# pedals.net
KiCad netlist of a schematic drawn in EAGLE
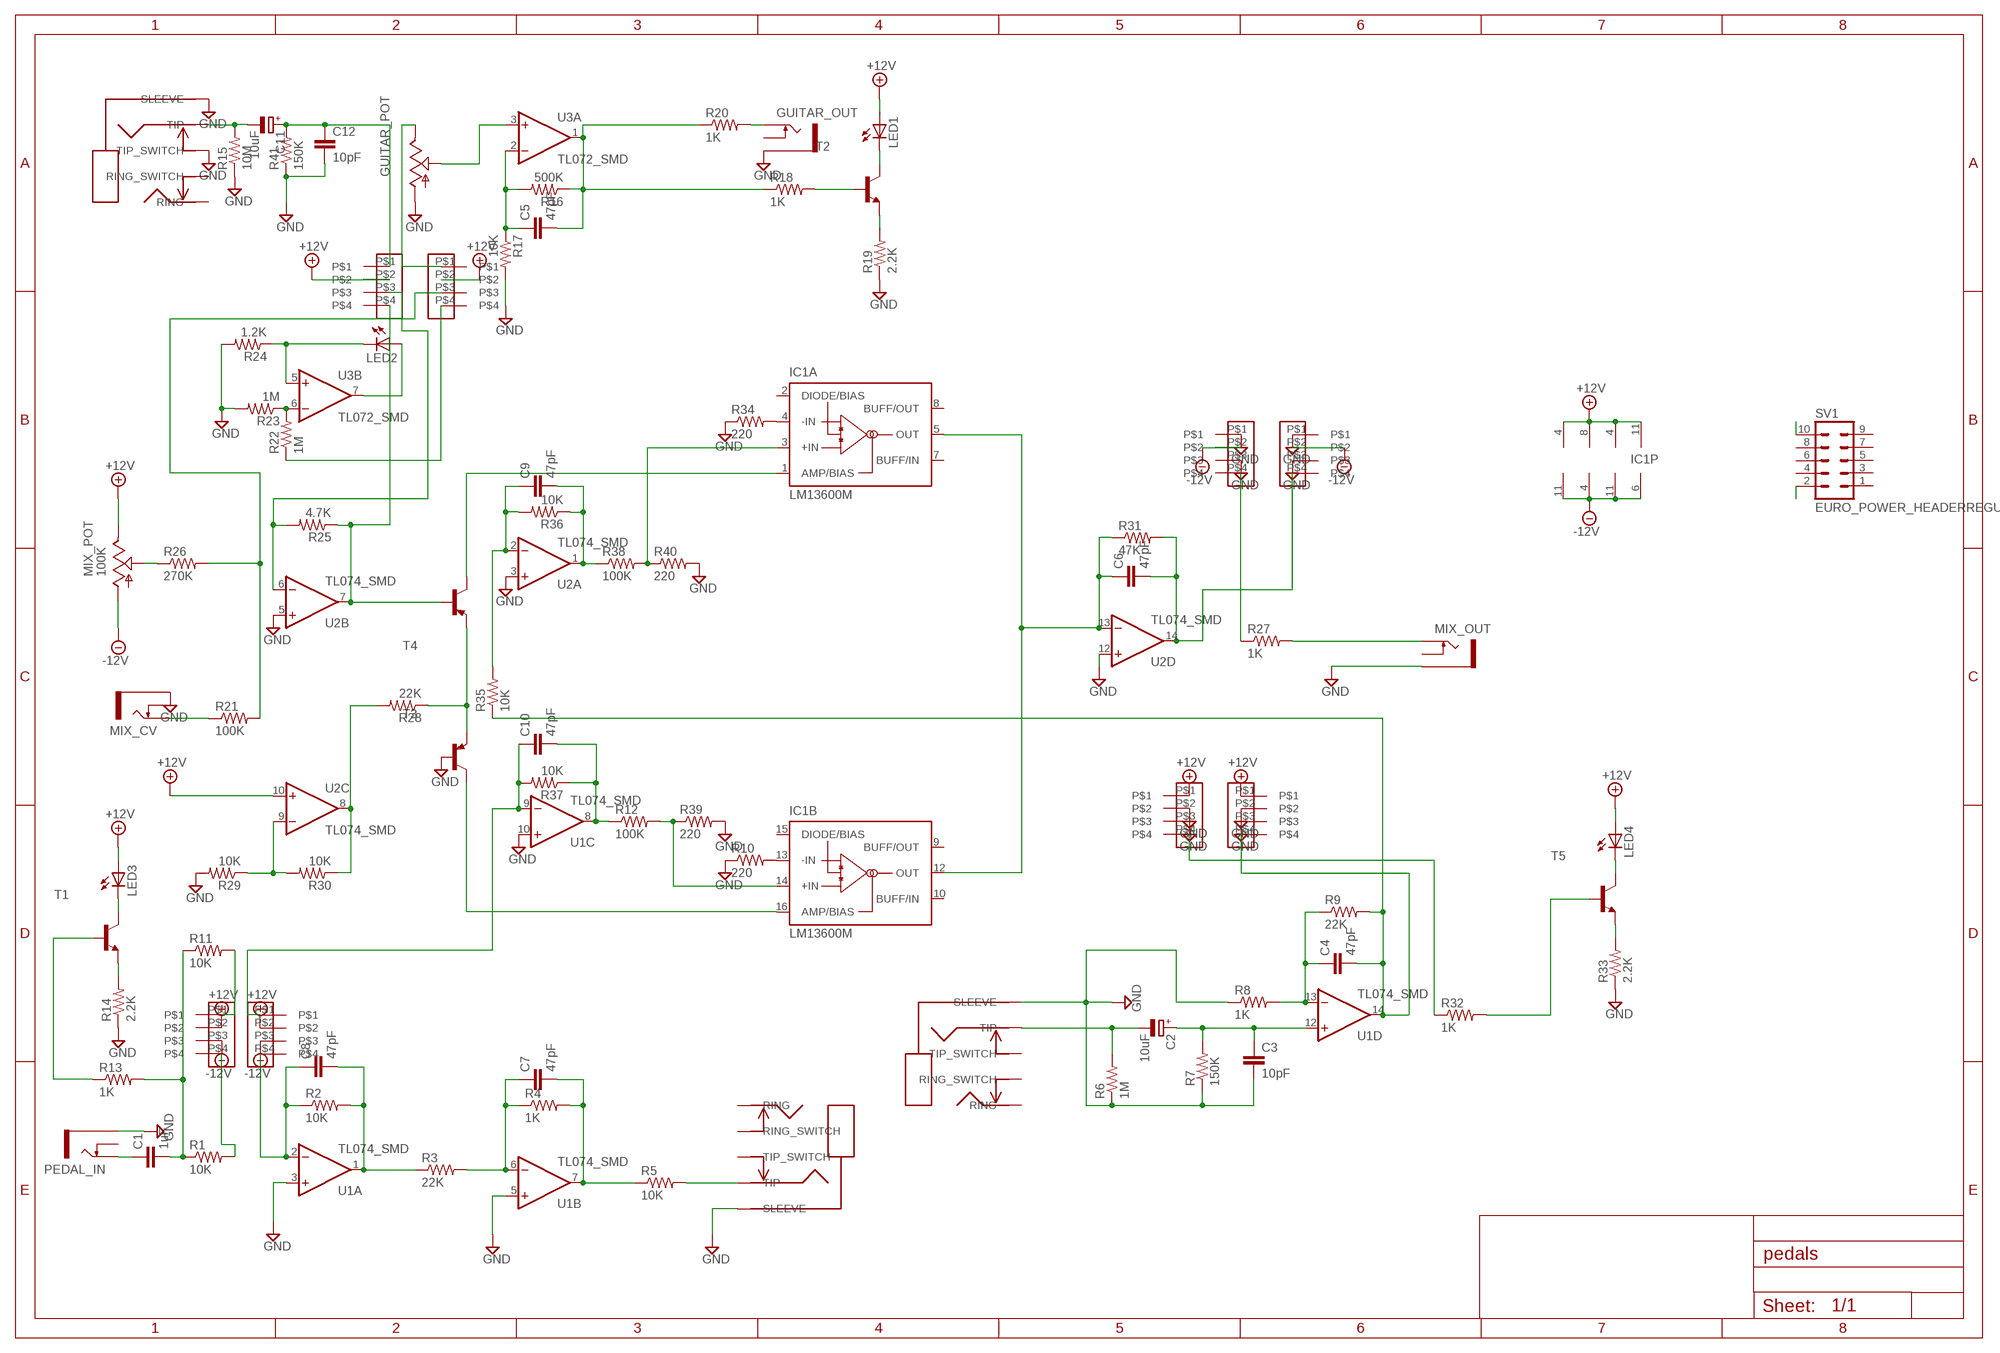
[diagram p0: schematic, sheet 1]

(export (version "E")
  (design (tool "Eeschema 10.0.6"))
  (components
    (comp (ref "C1")
      (value "1uF")
      (footprint "eagle-import:C0603")
      (libsource (lib "eagle-import") (part "C-EUC0603"))
    )
    (comp (ref "C2")
      (value "10uF")
      (footprint "eagle-import:PANASONIC_B")
      (libsource (lib "eagle-import") (part "CPOL-EUB"))
    )
    (comp (ref "C3")
      (value "10pF")
      (footprint "eagle-import:C0603")
      (libsource (lib "eagle-import") (part "C-EUC0603"))
    )
    (comp (ref "C4")
      (value "47pF")
      (footprint "eagle-import:C0603")
      (libsource (lib "eagle-import") (part "C-EUC0603"))
    )
    (comp (ref "C5")
      (value "47pF")
      (footprint "eagle-import:C0603")
      (libsource (lib "eagle-import") (part "C-EUC0603"))
    )
    (comp (ref "C6")
      (value "47pF")
      (footprint "eagle-import:C0603")
      (libsource (lib "eagle-import") (part "C-EUC0603"))
    )
    (comp (ref "C7")
      (value "47pF")
      (footprint "eagle-import:C0603")
      (libsource (lib "eagle-import") (part "C-EUC0603"))
    )
    (comp (ref "C8")
      (value "47pF")
      (footprint "eagle-import:C0603")
      (libsource (lib "eagle-import") (part "C-EUC0603"))
    )
    (comp (ref "C9")
      (value "47pF")
      (footprint "eagle-import:C0603")
      (libsource (lib "eagle-import") (part "C-EUC0603"))
    )
    (comp (ref "C10")
      (value "47pF")
      (footprint "eagle-import:C0603")
      (libsource (lib "eagle-import") (part "C-EUC0603"))
    )
    (comp (ref "C11")
      (value "10uF")
      (footprint "eagle-import:PANASONIC_B")
      (libsource (lib "eagle-import") (part "CPOL-EUB"))
    )
    (comp (ref "C12")
      (value "10pF")
      (footprint "eagle-import:C0603")
      (libsource (lib "eagle-import") (part "C-EUC0603"))
    )
    (comp (ref "GUITAR_INPUT")
      (value "WQP-PJ612A")
      (footprint "eagle-import:JACK")
      (libsource (lib "eagle-import") (part "WQP-PJ612A"))
    )
    (comp (ref "GUITAR_OUT")
      (value "THONKICONNNEW")
      (footprint "eagle-import:WQP-PJ301M-12_JACK")
      (libsource (lib "eagle-import") (part "THONKICONNNEW"))
    )
    (comp (ref "GUITAR_POT")
      (value "9MM_SNAP-IN_POT_")
      (footprint "eagle-import:9MM_SNAP-IN_POT")
      (libsource (lib "eagle-import") (part "9MM_SNAP-IN_POT_"))
    )
    (comp (ref "IC1")
      (value "LM13600M")
      (footprint "eagle-import:SO16")
      (libsource (lib "eagle-import") (part "LM13600M"))
    )
    (comp (ref "LB_B")
      (value "4PIN_HEADER")
      (footprint "eagle-import:4PIN")
      (libsource (lib "eagle-import") (part "4PIN_HEADER"))
    )
    (comp (ref "LB_O")
      (value "4PIN_HEADER")
      (footprint "eagle-import:4PIN")
      (libsource (lib "eagle-import") (part "4PIN_HEADER"))
    )
    (comp (ref "LED1")
      (value "LED3MM")
      (footprint "eagle-import:LED3MM")
      (libsource (lib "eagle-import") (part "LED3MM"))
    )
    (comp (ref "LED2")
      (value "LED3MM")
      (footprint "eagle-import:LED3MM")
      (libsource (lib "eagle-import") (part "LED3MM"))
    )
    (comp (ref "LED3")
      (value "LED3MM")
      (footprint "eagle-import:LED3MM")
      (libsource (lib "eagle-import") (part "LED3MM"))
    )
    (comp (ref "LED4")
      (value "LED3MM")
      (footprint "eagle-import:LED3MM")
      (libsource (lib "eagle-import") (part "led_259_LED3MM"))
    )
    (comp (ref "LO_B")
      (value "4PIN_HEADER")
      (footprint "eagle-import:4PIN")
      (libsource (lib "eagle-import") (part "4PIN_HEADER"))
    )
    (comp (ref "LO_O")
      (value "4PIN_HEADER")
      (footprint "eagle-import:4PIN")
      (libsource (lib "eagle-import") (part "4PIN_HEADER"))
    )
    (comp (ref "MIX_CV")
      (value "THONKICONNNEW")
      (footprint "eagle-import:WQP-PJ301M-12_JACK")
      (libsource (lib "eagle-import") (part "THONKICONNNEW"))
    )
    (comp (ref "MIX_OUT")
      (value "THONKICONNNEW")
      (footprint "eagle-import:WQP-PJ301M-12_JACK")
      (libsource (lib "eagle-import") (part "THONKICONNNEW"))
    )
    (comp (ref "MIX_POT")
      (value "100K")
      (footprint "eagle-import:9MM_SNAP-IN_POT")
      (libsource (lib "eagle-import") (part "9MM_SNAP-IN_POT_"))
    )
    (comp (ref "PEDAL-IN")
      (value "WQP-PJ612A")
      (footprint "eagle-import:JACK")
      (libsource (lib "eagle-import") (part "WQP-PJ612A"))
    )
    (comp (ref "PEDAL-OUT")
      (value "WQP-PJ612A")
      (footprint "eagle-import:JACK")
      (libsource (lib "eagle-import") (part "WQP-PJ612A"))
    )
    (comp (ref "PEDAL_IN")
      (value "THONKICONNNEW")
      (footprint "eagle-import:WQP-PJ301M-12_JACK")
      (libsource (lib "eagle-import") (part "THONKICONNNEW"))
    )
    (comp (ref "R1")
      (value "10K")
      (footprint "eagle-import:R0603")
      (libsource (lib "eagle-import") (part "R-US_R0603"))
    )
    (comp (ref "R2")
      (value "10K")
      (footprint "eagle-import:R0603")
      (libsource (lib "eagle-import") (part "R-US_R0603"))
    )
    (comp (ref "R3")
      (value "22K")
      (footprint "eagle-import:R0603")
      (libsource (lib "eagle-import") (part "R-US_R0603"))
    )
    (comp (ref "R4")
      (value "1K")
      (footprint "eagle-import:R0603")
      (libsource (lib "eagle-import") (part "R-US_R0603"))
    )
    (comp (ref "R5")
      (value "10K")
      (footprint "eagle-import:R0603")
      (libsource (lib "eagle-import") (part "R-US_R0603"))
    )
    (comp (ref "R6")
      (value "1M")
      (footprint "eagle-import:R0603")
      (libsource (lib "eagle-import") (part "R-US_R0603"))
    )
    (comp (ref "R7")
      (value "150K")
      (footprint "eagle-import:R0603")
      (libsource (lib "eagle-import") (part "R-US_R0603"))
    )
    (comp (ref "R8")
      (value "1K")
      (footprint "eagle-import:R0603")
      (libsource (lib "eagle-import") (part "R-US_R0603"))
    )
    (comp (ref "R9")
      (value "22K")
      (footprint "eagle-import:R0603")
      (libsource (lib "eagle-import") (part "R-US_R0603"))
    )
    (comp (ref "R10")
      (value "220")
      (footprint "eagle-import:R0603")
      (libsource (lib "eagle-import") (part "R-US_R0603"))
    )
    (comp (ref "R11")
      (value "10K")
      (footprint "eagle-import:R0603")
      (libsource (lib "eagle-import") (part "R-US_R0603"))
    )
    (comp (ref "R12")
      (value "100K")
      (footprint "eagle-import:R0603")
      (libsource (lib "eagle-import") (part "R-US_R0603"))
    )
    (comp (ref "R13")
      (value "1K")
      (footprint "eagle-import:R0603")
      (libsource (lib "eagle-import") (part "R-US_R0603"))
    )
    (comp (ref "R14")
      (value "2.2K")
      (footprint "eagle-import:R0603")
      (libsource (lib "eagle-import") (part "R-US_R0603"))
    )
    (comp (ref "R15")
      (value "10M")
      (footprint "eagle-import:R0603")
      (libsource (lib "eagle-import") (part "R-US_R0603"))
    )
    (comp (ref "R16")
      (value "500K")
      (footprint "eagle-import:R0603")
      (libsource (lib "eagle-import") (part "R-US_R0603"))
    )
    (comp (ref "R17")
      (value "10K")
      (footprint "eagle-import:R0603")
      (libsource (lib "eagle-import") (part "R-US_R0603"))
    )
    (comp (ref "R18")
      (value "1K")
      (footprint "eagle-import:R0603")
      (libsource (lib "eagle-import") (part "R-US_R0603"))
    )
    (comp (ref "R19")
      (value "2.2K")
      (footprint "eagle-import:R0603")
      (libsource (lib "eagle-import") (part "R-US_R0603"))
    )
    (comp (ref "R20")
      (value "1K")
      (footprint "eagle-import:R0603")
      (libsource (lib "eagle-import") (part "R-US_R0603"))
    )
    (comp (ref "R21")
      (value "100K")
      (footprint "eagle-import:R0603")
      (libsource (lib "eagle-import") (part "R-US_R0603"))
    )
    (comp (ref "R22")
      (value "1M")
      (footprint "eagle-import:R0603")
      (libsource (lib "eagle-import") (part "R-US_R0603"))
    )
    (comp (ref "R23")
      (value "1M")
      (footprint "eagle-import:R0603")
      (libsource (lib "eagle-import") (part "R-US_R0603"))
    )
    (comp (ref "R24")
      (value "1.2K")
      (footprint "eagle-import:R0603")
      (libsource (lib "eagle-import") (part "R-US_R0603"))
    )
    (comp (ref "R25")
      (value "4.7K")
      (footprint "eagle-import:R0603")
      (libsource (lib "eagle-import") (part "R-US_R0603"))
    )
    (comp (ref "R26")
      (value "270K")
      (footprint "eagle-import:R0603")
      (libsource (lib "eagle-import") (part "R-US_R0603"))
    )
    (comp (ref "R27")
      (value "1K")
      (footprint "eagle-import:R0603")
      (libsource (lib "eagle-import") (part "R-US_R0603"))
    )
    (comp (ref "R28")
      (value "22K")
      (footprint "eagle-import:R0603")
      (libsource (lib "eagle-import") (part "R-US_R0603"))
    )
    (comp (ref "R29")
      (value "10K")
      (footprint "eagle-import:R0603")
      (libsource (lib "eagle-import") (part "R-US_R0603"))
    )
    (comp (ref "R30")
      (value "10K")
      (footprint "eagle-import:R0603")
      (libsource (lib "eagle-import") (part "R-US_R0603"))
    )
    (comp (ref "R31")
      (value "47K")
      (footprint "eagle-import:R0603")
      (libsource (lib "eagle-import") (part "R-US_R0603"))
    )
    (comp (ref "R32")
      (value "1K")
      (footprint "eagle-import:R0603")
      (libsource (lib "eagle-import") (part "R-US_R0603"))
    )
    (comp (ref "R33")
      (value "2.2K")
      (footprint "eagle-import:R0603")
      (libsource (lib "eagle-import") (part "R-US_R0603"))
    )
    (comp (ref "R34")
      (value "220")
      (footprint "eagle-import:R0603")
      (libsource (lib "eagle-import") (part "R-US_R0603"))
    )
    (comp (ref "R35")
      (value "10K")
      (footprint "eagle-import:R0603")
      (libsource (lib "eagle-import") (part "R-US_R0603"))
    )
    (comp (ref "R36")
      (value "10K")
      (footprint "eagle-import:R0603")
      (libsource (lib "eagle-import") (part "R-US_R0603"))
    )
    (comp (ref "R37")
      (value "10K")
      (footprint "eagle-import:R0603")
      (libsource (lib "eagle-import") (part "R-US_R0603"))
    )
    (comp (ref "R38")
      (value "100K")
      (footprint "eagle-import:R0603")
      (libsource (lib "eagle-import") (part "R-US_R0603"))
    )
    (comp (ref "R39")
      (value "220")
      (footprint "eagle-import:R0603")
      (libsource (lib "eagle-import") (part "R-US_R0603"))
    )
    (comp (ref "R40")
      (value "220")
      (footprint "eagle-import:R0603")
      (libsource (lib "eagle-import") (part "R-US_R0603"))
    )
    (comp (ref "R41")
      (value "150K")
      (footprint "eagle-import:R0603")
      (libsource (lib "eagle-import") (part "R-US_R0603"))
    )
    (comp (ref "RB_B")
      (value "4PIN_HEADER")
      (footprint "eagle-import:4PIN")
      (libsource (lib "eagle-import") (part "4PIN_HEADER"))
    )
    (comp (ref "RB_O")
      (value "4PIN_HEADER")
      (footprint "eagle-import:4PIN")
      (libsource (lib "eagle-import") (part "4PIN_HEADER"))
    )
    (comp (ref "RO_B")
      (value "4PIN_HEADER")
      (footprint "eagle-import:4PIN")
      (libsource (lib "eagle-import") (part "4PIN_HEADER"))
    )
    (comp (ref "RO_O")
      (value "4PIN_HEADER")
      (footprint "eagle-import:4PIN")
      (libsource (lib "eagle-import") (part "4PIN_HEADER"))
    )
    (comp (ref "SV1")
      (value "EURO_POWER_HEADERREGULAR")
      (footprint "eagle-import:EURO_POWER_HEADER")
      (libsource (lib "eagle-import") (part "EURO_POWER_HEADERREGULAR"))
    )
    (comp (ref "T1")
      (value "MMBT3904LT1-NPN-SOT23-BEC")
      (footprint "eagle-import:SOT23-BEC")
      (libsource (lib "eagle-import") (part "-NPN-SOT23-BECMMBT3904LT1"))
    )
    (comp (ref "T2")
      (value "MMBT3904LT1-NPN-SOT23-BEC")
      (footprint "eagle-import:SOT23-BEC")
      (libsource (lib "eagle-import") (part "-NPN-SOT23-BECMMBT3904LT1"))
    )
    (comp (ref "T3")
      (value "BC857A-PNP-SOT23-BEC")
      (footprint "eagle-import:SOT23-BEC")
      (libsource (lib "eagle-import") (part "-PNP-SOT23-BECBC857A"))
    )
    (comp (ref "T4")
      (value "BC857A-PNP-SOT23-BEC")
      (footprint "eagle-import:SOT23-BEC")
      (libsource (lib "eagle-import") (part "-PNP-SOT23-BECBC857A"))
    )
    (comp (ref "T5")
      (value "MMBT3904LT1-NPN-SOT23-BEC")
      (footprint "eagle-import:SOT23-BEC")
      (libsource (lib "eagle-import") (part "-NPN-SOT23-BECMMBT3904LT1"))
    )
    (comp (ref "U1")
      (value "TL074_SMD")
      (footprint "eagle-import:SO14")
      (libsource (lib "eagle-import") (part "TL074_SMD"))
    )
    (comp (ref "U2")
      (value "TL074_SMD")
      (footprint "eagle-import:SO14")
      (libsource (lib "eagle-import") (part "TL074_SMD"))
    )
    (comp (ref "U3")
      (value "TL072_SMD")
      (footprint "eagle-import:SO08")
      (libsource (lib "eagle-import") (part "TL072_SMD"))
    )
  )
  (nets
    (net (code "1") (name "+12V") (class "Default")
      (node (ref "IC1") (pin "11") (pinfunction "V+_11") (pintype "power_in"))
      (node (ref "LB_B") (pin "P$2") (pinfunction "P$2_P$2") (pintype "bidirectional"))
      (node (ref "LB_O") (pin "P$2") (pinfunction "P$2_P$2") (pintype "bidirectional"))
      (node (ref "LED1") (pin "A") (pinfunction "A_A") (pintype "passive"))
      (node (ref "LED3") (pin "A") (pinfunction "A_A") (pintype "passive"))
      (node (ref "LED4") (pin "A") (pinfunction "A_A") (pintype "passive"))
      (node (ref "LO_B") (pin "P$2") (pinfunction "P$2_P$2") (pintype "bidirectional"))
      (node (ref "LO_O") (pin "P$2") (pinfunction "P$2_P$2") (pintype "bidirectional"))
      (node (ref "MIX_POT") (pin "3") (pinfunction "E_3") (pintype "passive"))
      (node (ref "RO_B") (pin "P$1") (pinfunction "P$1_P$1") (pintype "bidirectional"))
      (node (ref "RO_O") (pin "P$1") (pinfunction "P$1_P$1") (pintype "bidirectional"))
      (node (ref "U1") (pin "4") (pinfunction "V+_4") (pintype "power_in"))
      (node (ref "U2") (pin "10") (pinfunction "+IN_10") (pintype "input"))
      (node (ref "U2") (pin "4") (pinfunction "V+_4") (pintype "power_in"))
      (node (ref "U3") (pin "8") (pinfunction "V+_8") (pintype "power_in"))
    )
    (net (code "2") (name "-12V") (class "Default")
      (node (ref "IC1") (pin "6") (pinfunction "V-_6") (pintype "power_in"))
      (node (ref "LO_B") (pin "P$3") (pinfunction "P$3_P$3") (pintype "bidirectional"))
      (node (ref "LO_O") (pin "P$3") (pinfunction "P$3_P$3") (pintype "bidirectional"))
      (node (ref "MIX_POT") (pin "1") (pinfunction "A_1") (pintype "passive"))
      (node (ref "RB_B") (pin "P$2") (pinfunction "P$2_P$2") (pintype "bidirectional"))
      (node (ref "RB_O") (pin "P$2") (pinfunction "P$2_P$2") (pintype "bidirectional"))
      (node (ref "U1") (pin "11") (pinfunction "V-_11") (pintype "power_in"))
      (node (ref "U2") (pin "11") (pinfunction "V-_11") (pintype "power_in"))
      (node (ref "U3") (pin "4") (pinfunction "V-_4") (pintype "power_in"))
    )
    (net (code "3") (name "GND") (class "Default")
      (node (ref "C12") (pin "2") (pinfunction "2_2") (pintype "passive"))
      (node (ref "C3") (pin "2") (pinfunction "2_2") (pintype "passive"))
      (node (ref "GUITAR_INPUT") (pin "PIN1") (pinfunction "SLEEVE_PIN1") (pintype "output"))
      (node (ref "GUITAR_INPUT") (pin "PIN5") (pinfunction "TIP_SWITCH_PIN5") (pintype "input"))
      (node (ref "GUITAR_OUT") (pin "P$3_SLEEVE") (pinfunction "SLEEVE_P$3_SLEEVE") (pintype "passive"))
      (node (ref "GUITAR_POT") (pin "1") (pinfunction "A_1") (pintype "passive"))
      (node (ref "MIX_CV") (pin "P$3_SLEEVE") (pinfunction "SLEEVE_P$3_SLEEVE") (pintype "passive"))
      (node (ref "MIX_OUT") (pin "P$3_SLEEVE") (pinfunction "SLEEVE_P$3_SLEEVE") (pintype "passive"))
      (node (ref "PEDAL-IN") (pin "PIN1") (pinfunction "SLEEVE_PIN1") (pintype "output"))
      (node (ref "PEDAL-OUT") (pin "PIN1") (pinfunction "SLEEVE_PIN1") (pintype "output"))
      (node (ref "PEDAL_IN") (pin "P$3_SLEEVE") (pinfunction "SLEEVE_P$3_SLEEVE") (pintype "passive"))
      (node (ref "R10") (pin "1") (pinfunction "1_1") (pintype "passive"))
      (node (ref "R14") (pin "1") (pinfunction "1_1") (pintype "passive"))
      (node (ref "R15") (pin "1") (pinfunction "1_1") (pintype "passive"))
      (node (ref "R17") (pin "2") (pinfunction "2_2") (pintype "passive"))
      (node (ref "R19") (pin "1") (pinfunction "1_1") (pintype "passive"))
      (node (ref "R23") (pin "2") (pinfunction "2_2") (pintype "passive"))
      (node (ref "R24") (pin "2") (pinfunction "2_2") (pintype "passive"))
      (node (ref "R29") (pin "2") (pinfunction "2_2") (pintype "passive"))
      (node (ref "R33") (pin "1") (pinfunction "1_1") (pintype "passive"))
      (node (ref "R34") (pin "1") (pinfunction "1_1") (pintype "passive"))
      (node (ref "R39") (pin "2") (pinfunction "2_2") (pintype "passive"))
      (node (ref "R40") (pin "2") (pinfunction "2_2") (pintype "passive"))
      (node (ref "R41") (pin "1") (pinfunction "1_1") (pintype "passive"))
      (node (ref "R6") (pin "1") (pinfunction "1_1") (pintype "passive"))
      (node (ref "R7") (pin "1") (pinfunction "1_1") (pintype "passive"))
      (node (ref "R8") (pin "1") (pinfunction "1_1") (pintype "passive"))
      (node (ref "RB_B") (pin "P$1") (pinfunction "P$1_P$1") (pintype "bidirectional"))
      (node (ref "RB_B") (pin "P$3") (pinfunction "P$3_P$3") (pintype "bidirectional"))
      (node (ref "RB_O") (pin "P$1") (pinfunction "P$1_P$1") (pintype "bidirectional"))
      (node (ref "RB_O") (pin "P$3") (pinfunction "P$3_P$3") (pintype "bidirectional"))
      (node (ref "RO_B") (pin "P$2") (pinfunction "P$2_P$2") (pintype "bidirectional"))
      (node (ref "RO_B") (pin "P$3") (pinfunction "P$3_P$3") (pintype "bidirectional"))
      (node (ref "RO_O") (pin "P$2") (pinfunction "P$2_P$2") (pintype "bidirectional"))
      (node (ref "RO_O") (pin "P$3") (pinfunction "P$3_P$3") (pintype "bidirectional"))
      (node (ref "T3") (pin "B") (pinfunction "B_B") (pintype "passive"))
      (node (ref "U1") (pin "10") (pinfunction "+IN_10") (pintype "input"))
      (node (ref "U1") (pin "3") (pinfunction "+IN_3") (pintype "input"))
      (node (ref "U1") (pin "5") (pinfunction "+IN_5") (pintype "input"))
      (node (ref "U2") (pin "12") (pinfunction "+IN_12") (pintype "input"))
      (node (ref "U2") (pin "3") (pinfunction "+IN_3") (pintype "input"))
      (node (ref "U2") (pin "5") (pinfunction "+IN_5") (pintype "input"))
    )
    (net (code "4") (name "Net-(C1-Pad2)") (class "Default")
      (node (ref "C1") (pin "2") (pinfunction "2_2") (pintype "passive"))
      (node (ref "R1") (pin "1") (pinfunction "1_1") (pintype "passive"))
      (node (ref "R11") (pin "1") (pinfunction "1_1") (pintype "passive"))
      (node (ref "R13") (pin "2") (pinfunction "2_2") (pintype "passive"))
    )
    (net (code "5") (name "Net-(C11-Pad+)") (class "Default")
      (node (ref "C11") (pin "+") (pinfunction "+_+") (pintype "passive"))
      (node (ref "C12") (pin "1") (pinfunction "1_1") (pintype "passive"))
      (node (ref "LB_O") (pin "P$1") (pinfunction "P$1_P$1") (pintype "bidirectional"))
      (node (ref "R41") (pin "2") (pinfunction "2_2") (pintype "passive"))
    )
    (net (code "6") (name "Net-(GUITAR_INPUT-TIP)") (class "Default")
      (node (ref "C11") (pin "-") (pinfunction "-_-") (pintype "passive"))
      (node (ref "GUITAR_INPUT") (pin "PIN3") (pinfunction "TIP_PIN3") (pintype "output"))
      (node (ref "R15") (pin "2") (pinfunction "2_2") (pintype "passive"))
    )
    (net (code "7") (name "Net-(GUITAR_OUT-TIP)") (class "Default")
      (node (ref "GUITAR_OUT") (pin "P$1_TIP") (pinfunction "TIP_P$1_TIP") (pintype "passive"))
      (node (ref "R20") (pin "2") (pinfunction "2_2") (pintype "passive"))
    )
    (net (code "8") (name "Net-(GUITAR_POT-E)") (class "Default")
      (node (ref "GUITAR_POT") (pin "3") (pinfunction "E_3") (pintype "passive"))
      (node (ref "LB_B") (pin "P$1") (pinfunction "P$1_P$1") (pintype "bidirectional"))
    )
    (net (code "9") (name "Net-(GUITAR_POT-S)") (class "Default")
      (node (ref "GUITAR_POT") (pin "2") (pinfunction "S_2") (pintype "passive"))
      (node (ref "U3") (pin "3") (pinfunction "+IN_3") (pintype "input"))
    )
    (net (code "10") (name "Net-(IC1A-+IN)") (class "Default")
      (node (ref "IC1") (pin "3") (pinfunction "+IN_3") (pintype "input"))
      (node (ref "R38") (pin "2") (pinfunction "2_2") (pintype "passive"))
      (node (ref "R40") (pin "1") (pinfunction "1_1") (pintype "passive"))
    )
    (net (code "11") (name "Net-(IC1A--IN)") (class "Default")
      (node (ref "IC1") (pin "4") (pinfunction "-IN_4") (pintype "input"))
      (node (ref "R34") (pin "2") (pinfunction "2_2") (pintype "passive"))
    )
    (net (code "12") (name "Net-(IC1A-AMP{slash}BIAS)") (class "Default")
      (node (ref "IC1") (pin "1") (pinfunction "AMP/BIAS_1") (pintype "passive"))
      (node (ref "T4") (pin "C") (pinfunction "C_C") (pintype "passive"))
    )
    (net (code "13") (name "Net-(IC1A-OUT)") (class "Default")
      (node (ref "C6") (pin "1") (pinfunction "1_1") (pintype "passive"))
      (node (ref "IC1") (pin "12") (pinfunction "OUT_12") (pintype "output"))
      (node (ref "IC1") (pin "5") (pinfunction "OUT_5") (pintype "output"))
      (node (ref "R31") (pin "1") (pinfunction "1_1") (pintype "passive"))
      (node (ref "U2") (pin "13") (pinfunction "-IN_13") (pintype "input"))
    )
    (net (code "14") (name "Net-(IC1B-+IN)") (class "Default")
      (node (ref "IC1") (pin "14") (pinfunction "+IN_14") (pintype "input"))
      (node (ref "R12") (pin "2") (pinfunction "2_2") (pintype "passive"))
      (node (ref "R39") (pin "1") (pinfunction "1_1") (pintype "passive"))
    )
    (net (code "15") (name "Net-(IC1B--IN)") (class "Default")
      (node (ref "IC1") (pin "13") (pinfunction "-IN_13") (pintype "input"))
      (node (ref "R10") (pin "2") (pinfunction "2_2") (pintype "passive"))
    )
    (net (code "16") (name "Net-(IC1B-AMP{slash}BIAS)") (class "Default")
      (node (ref "IC1") (pin "16") (pinfunction "AMP/BIAS_16") (pintype "passive"))
      (node (ref "T3") (pin "C") (pinfunction "C_C") (pintype "passive"))
    )
    (net (code "17") (name "Net-(LB_B-PadP$3)") (class "Default")
      (node (ref "LB_B") (pin "P$3") (pinfunction "P$3_P$3") (pintype "bidirectional"))
      (node (ref "R21") (pin "2") (pinfunction "2_2") (pintype "passive"))
      (node (ref "R26") (pin "2") (pinfunction "2_2") (pintype "passive"))
    )
    (net (code "18") (name "Net-(LB_B-PadP$4)") (class "Default")
      (node (ref "LB_B") (pin "P$4") (pinfunction "P$4_P$4") (pintype "bidirectional"))
      (node (ref "R22") (pin "1") (pinfunction "1_1") (pintype "passive"))
    )
    (net (code "19") (name "Net-(LED1-C)") (class "Default")
      (node (ref "LED1") (pin "K") (pinfunction "C_K") (pintype "passive"))
      (node (ref "T2") (pin "C") (pinfunction "C_C") (pintype "passive"))
    )
    (net (code "20") (name "Net-(LED2-C)") (class "Default")
      (node (ref "LED2") (pin "K") (pinfunction "C_K") (pintype "passive"))
      (node (ref "R24") (pin "1") (pinfunction "1_1") (pintype "passive"))
      (node (ref "U3") (pin "5") (pinfunction "+IN_5") (pintype "input"))
    )
    (net (code "21") (name "Net-(LED3-C)") (class "Default")
      (node (ref "LED3") (pin "K") (pinfunction "C_K") (pintype "passive"))
      (node (ref "T1") (pin "C") (pinfunction "C_C") (pintype "passive"))
    )
    (net (code "22") (name "Net-(LED4-C)") (class "Default")
      (node (ref "LED4") (pin "K") (pinfunction "C_K") (pintype "passive"))
      (node (ref "T5") (pin "C") (pinfunction "C_C") (pintype "passive"))
    )
    (net (code "23") (name "Net-(LO_B-PadP$1)") (class "Default")
      (node (ref "LO_B") (pin "P$1") (pinfunction "P$1_P$1") (pintype "bidirectional"))
      (node (ref "R11") (pin "2") (pinfunction "2_2") (pintype "passive"))
    )
    (net (code "24") (name "Net-(LO_B-PadP$4)") (class "Default")
      (node (ref "LO_B") (pin "P$4") (pinfunction "P$4_P$4") (pintype "bidirectional"))
      (node (ref "R1") (pin "2") (pinfunction "2_2") (pintype "passive"))
    )
    (net (code "25") (name "Net-(MIX_CV-TIP)") (class "Default")
      (node (ref "MIX_CV") (pin "P$1_TIP") (pinfunction "TIP_P$1_TIP") (pintype "passive"))
      (node (ref "R21") (pin "1") (pinfunction "1_1") (pintype "passive"))
    )
    (net (code "26") (name "Net-(MIX_OUT-TIP)") (class "Default")
      (node (ref "MIX_OUT") (pin "P$1_TIP") (pinfunction "TIP_P$1_TIP") (pintype "passive"))
      (node (ref "R27") (pin "2") (pinfunction "2_2") (pintype "passive"))
    )
    (net (code "27") (name "Net-(MIX_POT-S)") (class "Default")
      (node (ref "MIX_POT") (pin "2") (pinfunction "S_2") (pintype "passive"))
      (node (ref "R26") (pin "1") (pinfunction "1_1") (pintype "passive"))
    )
    (net (code "28") (name "Net-(PEDAL-IN-TIP)") (class "Default")
      (node (ref "C2") (pin "-") (pinfunction "-_-") (pintype "passive"))
      (node (ref "PEDAL-IN") (pin "PIN3") (pinfunction "TIP_PIN3") (pintype "output"))
      (node (ref "R6") (pin "2") (pinfunction "2_2") (pintype "passive"))
    )
    (net (code "29") (name "Net-(PEDAL-OUT-TIP)") (class "Default")
      (node (ref "PEDAL-OUT") (pin "PIN3") (pinfunction "TIP_PIN3") (pintype "output"))
      (node (ref "R5") (pin "2") (pinfunction "2_2") (pintype "passive"))
    )
    (net (code "30") (name "Net-(PEDAL_IN-TIP)") (class "Default")
      (node (ref "C1") (pin "1") (pinfunction "1_1") (pintype "passive"))
      (node (ref "PEDAL_IN") (pin "P$1_TIP") (pinfunction "TIP_P$1_TIP") (pintype "passive"))
    )
    (net (code "31") (name "Net-(R13-Pad1)") (class "Default")
      (node (ref "R13") (pin "1") (pinfunction "1_1") (pintype "passive"))
      (node (ref "T1") (pin "B") (pinfunction "B_B") (pintype "passive"))
    )
    (net (code "32") (name "Net-(R14-Pad2)") (class "Default")
      (node (ref "R14") (pin "2") (pinfunction "2_2") (pintype "passive"))
      (node (ref "T1") (pin "E") (pinfunction "E_E") (pintype "passive"))
    )
    (net (code "33") (name "Net-(R18-Pad2)") (class "Default")
      (node (ref "R18") (pin "2") (pinfunction "2_2") (pintype "passive"))
      (node (ref "T2") (pin "B") (pinfunction "B_B") (pintype "passive"))
    )
    (net (code "34") (name "Net-(R19-Pad2)") (class "Default")
      (node (ref "R19") (pin "2") (pinfunction "2_2") (pintype "passive"))
      (node (ref "T2") (pin "E") (pinfunction "E_E") (pintype "passive"))
    )
    (net (code "35") (name "Net-(R27-Pad1)") (class "Default")
      (node (ref "R27") (pin "1") (pinfunction "1_1") (pintype "passive"))
      (node (ref "RB_B") (pin "P$4") (pinfunction "P$4_P$4") (pintype "bidirectional"))
    )
    (net (code "36") (name "Net-(R28-Pad1)") (class "Default")
      (node (ref "R28") (pin "1") (pinfunction "1_1") (pintype "passive"))
      (node (ref "T3") (pin "E") (pinfunction "E_E") (pintype "passive"))
      (node (ref "T4") (pin "E") (pinfunction "E_E") (pintype "passive"))
    )
    (net (code "37") (name "Net-(R32-Pad1)") (class "Default")
      (node (ref "R32") (pin "1") (pinfunction "1_1") (pintype "passive"))
      (node (ref "RO_B") (pin "P$4") (pinfunction "P$4_P$4") (pintype "bidirectional"))
    )
    (net (code "38") (name "Net-(R32-Pad2)") (class "Default")
      (node (ref "R32") (pin "2") (pinfunction "2_2") (pintype "passive"))
      (node (ref "T5") (pin "B") (pinfunction "B_B") (pintype "passive"))
    )
    (net (code "39") (name "Net-(R33-Pad2)") (class "Default")
      (node (ref "R33") (pin "2") (pinfunction "2_2") (pintype "passive"))
      (node (ref "T5") (pin "E") (pinfunction "E_E") (pintype "passive"))
    )
    (net (code "40") (name "Net-(U1A--IN)") (class "Default")
      (node (ref "C8") (pin "1") (pinfunction "1_1") (pintype "passive"))
      (node (ref "LO_O") (pin "P$4") (pinfunction "P$4_P$4") (pintype "bidirectional"))
      (node (ref "R2") (pin "1") (pinfunction "1_1") (pintype "passive"))
      (node (ref "U1") (pin "2") (pinfunction "-IN_2") (pintype "input"))
    )
    (net (code "41") (name "Net-(U1A-OUT)") (class "Default")
      (node (ref "C8") (pin "2") (pinfunction "2_2") (pintype "passive"))
      (node (ref "R2") (pin "2") (pinfunction "2_2") (pintype "passive"))
      (node (ref "R3") (pin "1") (pinfunction "1_1") (pintype "passive"))
      (node (ref "U1") (pin "1") (pinfunction "OUT_1") (pintype "output"))
    )
    (net (code "42") (name "Net-(U1B--IN)") (class "Default")
      (node (ref "C7") (pin "1") (pinfunction "1_1") (pintype "passive"))
      (node (ref "R3") (pin "2") (pinfunction "2_2") (pintype "passive"))
      (node (ref "R4") (pin "1") (pinfunction "1_1") (pintype "passive"))
      (node (ref "U1") (pin "6") (pinfunction "-IN_6") (pintype "input"))
    )
    (net (code "43") (name "Net-(U1B-OUT)") (class "Default")
      (node (ref "C7") (pin "2") (pinfunction "2_2") (pintype "passive"))
      (node (ref "R4") (pin "2") (pinfunction "2_2") (pintype "passive"))
      (node (ref "R5") (pin "1") (pinfunction "1_1") (pintype "passive"))
      (node (ref "U1") (pin "7") (pinfunction "OUT_7") (pintype "output"))
    )
    (net (code "44") (name "Net-(U1C--IN)") (class "Default")
      (node (ref "C10") (pin "1") (pinfunction "1_1") (pintype "passive"))
      (node (ref "LO_O") (pin "P$1") (pinfunction "P$1_P$1") (pintype "bidirectional"))
      (node (ref "R37") (pin "2") (pinfunction "2_2") (pintype "passive"))
      (node (ref "U1") (pin "9") (pinfunction "-IN_9") (pintype "input"))
    )
    (net (code "45") (name "Net-(U1C-OUT)") (class "Default")
      (node (ref "C10") (pin "2") (pinfunction "2_2") (pintype "passive"))
      (node (ref "R12") (pin "1") (pinfunction "1_1") (pintype "passive"))
      (node (ref "R37") (pin "1") (pinfunction "1_1") (pintype "passive"))
      (node (ref "U1") (pin "8") (pinfunction "OUT_8") (pintype "output"))
    )
    (net (code "46") (name "Net-(U1D-+IN)") (class "Default")
      (node (ref "C2") (pin "+") (pinfunction "+_+") (pintype "passive"))
      (node (ref "C3") (pin "1") (pinfunction "1_1") (pintype "passive"))
      (node (ref "R7") (pin "2") (pinfunction "2_2") (pintype "passive"))
      (node (ref "U1") (pin "12") (pinfunction "+IN_12") (pintype "input"))
    )
    (net (code "47") (name "Net-(U1D--IN)") (class "Default")
      (node (ref "C4") (pin "1") (pinfunction "1_1") (pintype "passive"))
      (node (ref "R8") (pin "2") (pinfunction "2_2") (pintype "passive"))
      (node (ref "R9") (pin "1") (pinfunction "1_1") (pintype "passive"))
      (node (ref "U1") (pin "13") (pinfunction "-IN_13") (pintype "input"))
    )
    (net (code "48") (name "Net-(U1D-OUT)") (class "Default")
      (node (ref "C4") (pin "2") (pinfunction "2_2") (pintype "passive"))
      (node (ref "R35") (pin "1") (pinfunction "1_1") (pintype "passive"))
      (node (ref "R9") (pin "2") (pinfunction "2_2") (pintype "passive"))
      (node (ref "RO_O") (pin "P$4") (pinfunction "P$4_P$4") (pintype "bidirectional"))
      (node (ref "U1") (pin "14") (pinfunction "OUT_14") (pintype "output"))
    )
    (net (code "49") (name "Net-(U2A--IN)") (class "Default")
      (node (ref "C9") (pin "1") (pinfunction "1_1") (pintype "passive"))
      (node (ref "R35") (pin "2") (pinfunction "2_2") (pintype "passive"))
      (node (ref "R36") (pin "2") (pinfunction "2_2") (pintype "passive"))
      (node (ref "U2") (pin "2") (pinfunction "-IN_2") (pintype "input"))
    )
    (net (code "50") (name "Net-(U2A-OUT)") (class "Default")
      (node (ref "C9") (pin "2") (pinfunction "2_2") (pintype "passive"))
      (node (ref "R36") (pin "1") (pinfunction "1_1") (pintype "passive"))
      (node (ref "R38") (pin "1") (pinfunction "1_1") (pintype "passive"))
      (node (ref "U2") (pin "1") (pinfunction "OUT_1") (pintype "output"))
    )
    (net (code "51") (name "Net-(U2B--IN)") (class "Default")
      (node (ref "LB_O") (pin "P$3") (pinfunction "P$3_P$3") (pintype "bidirectional"))
      (node (ref "R25") (pin "2") (pinfunction "2_2") (pintype "passive"))
      (node (ref "U2") (pin "6") (pinfunction "-IN_6") (pintype "input"))
    )
    (net (code "52") (name "Net-(U2B-OUT)") (class "Default")
      (node (ref "LB_O") (pin "P$4") (pinfunction "P$4_P$4") (pintype "bidirectional"))
      (node (ref "R25") (pin "1") (pinfunction "1_1") (pintype "passive"))
      (node (ref "T4") (pin "B") (pinfunction "B_B") (pintype "passive"))
      (node (ref "U2") (pin "7") (pinfunction "OUT_7") (pintype "output"))
    )
    (net (code "53") (name "Net-(U2C--IN)") (class "Default")
      (node (ref "R29") (pin "1") (pinfunction "1_1") (pintype "passive"))
      (node (ref "R30") (pin "2") (pinfunction "2_2") (pintype "passive"))
      (node (ref "U2") (pin "9") (pinfunction "-IN_9") (pintype "input"))
    )
    (net (code "54") (name "Net-(U2C-OUT)") (class "Default")
      (node (ref "R28") (pin "2") (pinfunction "2_2") (pintype "passive"))
      (node (ref "R30") (pin "1") (pinfunction "1_1") (pintype "passive"))
      (node (ref "U2") (pin "8") (pinfunction "OUT_8") (pintype "output"))
    )
    (net (code "55") (name "Net-(U2D-OUT)") (class "Default")
      (node (ref "C6") (pin "2") (pinfunction "2_2") (pintype "passive"))
      (node (ref "R31") (pin "2") (pinfunction "2_2") (pintype "passive"))
      (node (ref "RB_O") (pin "P$4") (pinfunction "P$4_P$4") (pintype "bidirectional"))
      (node (ref "U2") (pin "14") (pinfunction "OUT_14") (pintype "output"))
    )
    (net (code "56") (name "Net-(U3A--IN)") (class "Default")
      (node (ref "C5") (pin "1") (pinfunction "1_1") (pintype "passive"))
      (node (ref "R16") (pin "2") (pinfunction "2_2") (pintype "passive"))
      (node (ref "R17") (pin "1") (pinfunction "1_1") (pintype "passive"))
      (node (ref "U3") (pin "2") (pinfunction "-IN_2") (pintype "input"))
    )
    (net (code "57") (name "Net-(U3A-OUT)") (class "Default")
      (node (ref "C5") (pin "2") (pinfunction "2_2") (pintype "passive"))
      (node (ref "R16") (pin "1") (pinfunction "1_1") (pintype "passive"))
      (node (ref "R18") (pin "1") (pinfunction "1_1") (pintype "passive"))
      (node (ref "R20") (pin "1") (pinfunction "1_1") (pintype "passive"))
      (node (ref "U3") (pin "1") (pinfunction "OUT_1") (pintype "output"))
    )
    (net (code "58") (name "Net-(U3B--IN)") (class "Default")
      (node (ref "R22") (pin "2") (pinfunction "2_2") (pintype "passive"))
      (node (ref "R23") (pin "1") (pinfunction "1_1") (pintype "passive"))
      (node (ref "U3") (pin "6") (pinfunction "-IN_6") (pintype "input"))
    )
    (net (code "59") (name "Net-(U3B-OUT)") (class "Default")
      (node (ref "LED2") (pin "A") (pinfunction "A_A") (pintype "passive"))
      (node (ref "U3") (pin "7") (pinfunction "OUT_7") (pintype "output"))
    )
    (net (code "60") (name "unconnected-(GUITAR_INPUT-RING-PadPIN2)") (class "Default")
      (node (ref "GUITAR_INPUT") (pin "PIN2") (pinfunction "RING_PIN2") (pintype "output"))
    )
    (net (code "61") (name "unconnected-(GUITAR_INPUT-RING_SWITCH-PadPIN4)") (class "Default")
      (node (ref "GUITAR_INPUT") (pin "PIN4") (pinfunction "RING_SWITCH_PIN4") (pintype "input"))
    )
    (net (code "62") (name "unconnected-(GUITAR_OUT-SWITCH-PadP$2_SWITCH)") (class "Default")
      (node (ref "GUITAR_OUT") (pin "P$2_SWITCH") (pinfunction "SWITCH_P$2_SWITCH") (pintype "passive"))
    )
    (net (code "63") (name "unconnected-(IC1A-BUFF{slash}IN-Pad7)") (class "Default")
      (node (ref "IC1") (pin "7") (pinfunction "BUFF/IN_7") (pintype "input"))
    )
    (net (code "64") (name "unconnected-(IC1A-BUFF{slash}OUT-Pad8)") (class "Default")
      (node (ref "IC1") (pin "8") (pinfunction "BUFF/OUT_8") (pintype "output"))
    )
    (net (code "65") (name "unconnected-(IC1A-DIODE{slash}BIAS-Pad2)") (class "Default")
      (node (ref "IC1") (pin "2") (pinfunction "DIODE/BIAS_2") (pintype "passive"))
    )
    (net (code "66") (name "unconnected-(IC1B-BUFF{slash}IN-Pad10)") (class "Default")
      (node (ref "IC1") (pin "10") (pinfunction "BUFF/IN_10") (pintype "input"))
    )
    (net (code "67") (name "unconnected-(IC1B-BUFF{slash}OUT-Pad9)") (class "Default")
      (node (ref "IC1") (pin "9") (pinfunction "BUFF/OUT_9") (pintype "output"))
    )
    (net (code "68") (name "unconnected-(IC1B-DIODE{slash}BIAS-Pad15)") (class "Default")
      (node (ref "IC1") (pin "15") (pinfunction "DIODE/BIAS_15") (pintype "passive"))
    )
    (net (code "69") (name "unconnected-(MIX_CV-SWITCH-PadP$2_SWITCH)") (class "Default")
      (node (ref "MIX_CV") (pin "P$2_SWITCH") (pinfunction "SWITCH_P$2_SWITCH") (pintype "passive"))
    )
    (net (code "70") (name "unconnected-(MIX_OUT-SWITCH-PadP$2_SWITCH)") (class "Default")
      (node (ref "MIX_OUT") (pin "P$2_SWITCH") (pinfunction "SWITCH_P$2_SWITCH") (pintype "passive"))
    )
    (net (code "71") (name "unconnected-(PEDAL-IN-RING-PadPIN2)") (class "Default")
      (node (ref "PEDAL-IN") (pin "PIN2") (pinfunction "RING_PIN2") (pintype "output"))
    )
    (net (code "72") (name "unconnected-(PEDAL-IN-RING_SWITCH-PadPIN4)") (class "Default")
      (node (ref "PEDAL-IN") (pin "PIN4") (pinfunction "RING_SWITCH_PIN4") (pintype "input"))
    )
    (net (code "73") (name "unconnected-(PEDAL-IN-TIP_SWITCH-PadPIN5)") (class "Default")
      (node (ref "PEDAL-IN") (pin "PIN5") (pinfunction "TIP_SWITCH_PIN5") (pintype "input"))
    )
    (net (code "74") (name "unconnected-(PEDAL-OUT-RING-PadPIN2)") (class "Default")
      (node (ref "PEDAL-OUT") (pin "PIN2") (pinfunction "RING_PIN2") (pintype "output"))
    )
    (net (code "75") (name "unconnected-(PEDAL-OUT-RING_SWITCH-PadPIN4)") (class "Default")
      (node (ref "PEDAL-OUT") (pin "PIN4") (pinfunction "RING_SWITCH_PIN4") (pintype "input"))
    )
    (net (code "76") (name "unconnected-(PEDAL-OUT-TIP_SWITCH-PadPIN5)") (class "Default")
      (node (ref "PEDAL-OUT") (pin "PIN5") (pinfunction "TIP_SWITCH_PIN5") (pintype "input"))
    )
    (net (code "77") (name "unconnected-(PEDAL_IN-SWITCH-PadP$2_SWITCH)") (class "Default")
      (node (ref "PEDAL_IN") (pin "P$2_SWITCH") (pinfunction "SWITCH_P$2_SWITCH") (pintype "passive"))
    )
    (net (code "78") (name "unconnected-(SV1-Pad1)") (class "Default")
      (node (ref "SV1") (pin "1") (pinfunction "1_1") (pintype "passive"))
    )
    (net (code "79") (name "unconnected-(SV1-Pad2)") (class "Default")
      (node (ref "SV1") (pin "2") (pinfunction "2_2") (pintype "passive"))
    )
    (net (code "80") (name "unconnected-(SV1-Pad3)") (class "Default")
      (node (ref "SV1") (pin "3") (pinfunction "3_3") (pintype "passive"))
    )
    (net (code "81") (name "unconnected-(SV1-Pad4)") (class "Default")
      (node (ref "SV1") (pin "4") (pinfunction "4_4") (pintype "passive"))
    )
    (net (code "82") (name "unconnected-(SV1-Pad5)") (class "Default")
      (node (ref "SV1") (pin "5") (pinfunction "5_5") (pintype "passive"))
    )
    (net (code "83") (name "unconnected-(SV1-Pad6)") (class "Default")
      (node (ref "SV1") (pin "6") (pinfunction "6_6") (pintype "passive"))
    )
    (net (code "84") (name "unconnected-(SV1-Pad7)") (class "Default")
      (node (ref "SV1") (pin "7") (pinfunction "7_7") (pintype "passive"))
    )
    (net (code "85") (name "unconnected-(SV1-Pad8)") (class "Default")
      (node (ref "SV1") (pin "8") (pinfunction "8_8") (pintype "passive"))
    )
    (net (code "86") (name "unconnected-(SV1-Pad9)") (class "Default")
      (node (ref "SV1") (pin "9") (pinfunction "9_9") (pintype "passive"))
    )
    (net (code "87") (name "unconnected-(SV1-Pad10)") (class "Default")
      (node (ref "SV1") (pin "10") (pinfunction "10_10") (pintype "passive"))
    )
  )
)
